# piezo-preamp-tickler_V0-5b.net
KiCad netlist of a schematic drawn in EAGLE
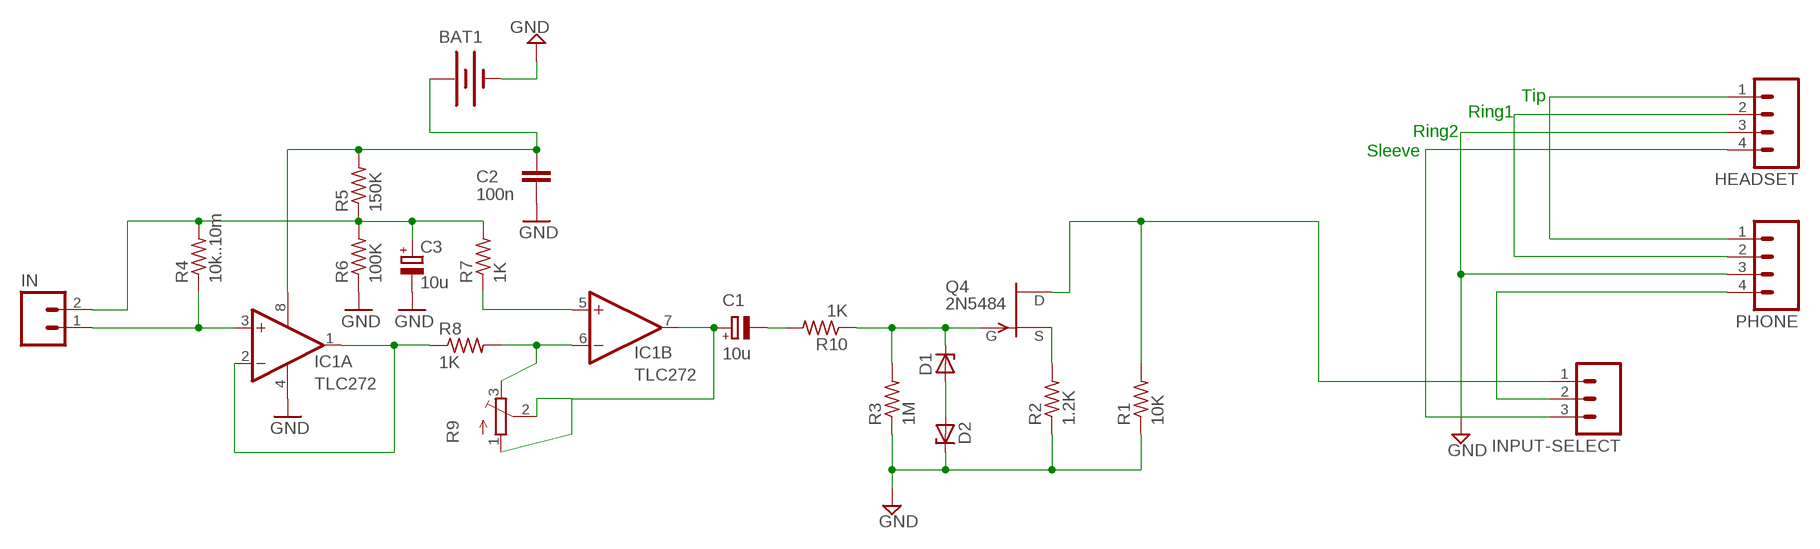
[diagram p0: schematic, sheet 1]

(export (version "E")
  (design (tool "Eeschema 10.0.6"))
  (components
    (comp (ref "BAT1")
      (value "BATTERYA23")
      (footprint "eagle-import:BATTERY-A23")
      (libsource (lib "eagle-import") (part "BATTERYA23"))
    )
    (comp (ref "C1")
      (value "10u")
      (footprint "eagle-import:E2,5-5")
      (libsource (lib "eagle-import") (part "CPOL-EUE2.5-5"))
    )
    (comp (ref "C2")
      (value "100n")
      (footprint "eagle-import:C025-025X050")
      (libsource (lib "eagle-import") (part "C-EU025-025X050"))
    )
    (comp (ref "C3")
      (value "10u")
      (footprint "eagle-import:E2,5-5")
      (libsource (lib "eagle-import") (part "CPOL-EUE2.5-5"))
    )
    (comp (ref "D1")
      (value "1N821")
      (footprint "eagle-import:DO35Z10")
      (libsource (lib "eagle-import") (part "1N821"))
    )
    (comp (ref "D2")
      (value "1N821")
      (footprint "eagle-import:DO35Z10")
      (libsource (lib "eagle-import") (part "1N821"))
    )
    (comp (ref "HEADSET")
      (value "M04LOCK")
      (footprint "eagle-import:1X04_LOCK")
      (libsource (lib "eagle-import") (part "M04LOCK"))
    )
    (comp (ref "IC1")
      (value "TLC272")
      (footprint "eagle-import:DIL08")
      (libsource (lib "eagle-import") (part "TLC272P"))
    )
    (comp (ref "IN")
      (value "M02LOCK")
      (footprint "eagle-import:1X02_LOCK")
      (libsource (lib "eagle-import") (part "M02LOCK"))
    )
    (comp (ref "INPUT-SELECT")
      (value "M03LOCK")
      (footprint "eagle-import:1X03_LOCK")
      (libsource (lib "eagle-import") (part "M03LOCK"))
    )
    (comp (ref "PHONE")
      (value "M04LOCK")
      (footprint "eagle-import:1X04_LOCK")
      (libsource (lib "eagle-import") (part "M04LOCK"))
    )
    (comp (ref "Q4")
      (value "2N5484")
      (footprint "eagle-import:TO92-")
      (libsource (lib "eagle-import") (part "?5482N4"))
    )
    (comp (ref "R1")
      (value "10K")
      (footprint "eagle-import:0204V")
      (libsource (lib "eagle-import") (part "R-US_0204/2V"))
    )
    (comp (ref "R2")
      (value "1.2K")
      (footprint "eagle-import:0204V")
      (libsource (lib "eagle-import") (part "R-US_0204/2V"))
    )
    (comp (ref "R3")
      (value "1M")
      (footprint "eagle-import:0204V")
      (libsource (lib "eagle-import") (part "R-US_0204/2V"))
    )
    (comp (ref "R4")
      (value "10k..10m")
      (footprint "eagle-import:0204V")
      (libsource (lib "eagle-import") (part "R-US_0204/2V"))
    )
    (comp (ref "R5")
      (value "150K")
      (footprint "eagle-import:0204V")
      (libsource (lib "eagle-import") (part "R-US_0204/2V"))
    )
    (comp (ref "R6")
      (value "100K")
      (footprint "eagle-import:0204V")
      (libsource (lib "eagle-import") (part "R-US_0204/2V"))
    )
    (comp (ref "R7")
      (value "1K")
      (footprint "eagle-import:0204V")
      (libsource (lib "eagle-import") (part "R-US_0204/2V"))
    )
    (comp (ref "R8")
      (value "1K")
      (footprint "eagle-import:0204V")
      (libsource (lib "eagle-import") (part "R-US_0204/2V"))
    )
    (comp (ref "R9")
      (value "TRIMPOT3386")
      (footprint "eagle-import:TRIM-3386")
      (libsource (lib "eagle-import") (part "TRIMPOT3386"))
    )
    (comp (ref "R10")
      (value "1K")
      (footprint "eagle-import:0204V")
      (libsource (lib "eagle-import") (part "R-US_0204/2V"))
    )
  )
  (nets
    (net (code "1") (name "GND") (class "Default")
      (node (ref "BAT1") (pin "GND@1") (pinfunction "-_GND@1") (pintype "power_in"))
      (node (ref "C2") (pin "1") (pinfunction "1_1") (pintype "passive"))
      (node (ref "C3") (pin "-") (pinfunction "-_-") (pintype "passive"))
      (node (ref "D2") (pin "C") (pinfunction "C_C") (pintype "passive"))
      (node (ref "HEADSET") (pin "3") (pinfunction "3_3") (pintype "passive"))
      (node (ref "IC1") (pin "4") (pinfunction "V-_4") (pintype "power_in"))
      (node (ref "PHONE") (pin "3") (pinfunction "3_3") (pintype "passive"))
      (node (ref "R1") (pin "1") (pinfunction "1_1") (pintype "passive"))
      (node (ref "R2") (pin "1") (pinfunction "1_1") (pintype "passive"))
      (node (ref "R3") (pin "1") (pinfunction "1_1") (pintype "passive"))
      (node (ref "R6") (pin "1") (pinfunction "1_1") (pintype "passive"))
    )
    (net (code "2") (name "Net-(BAT1-+)") (class "Default")
      (node (ref "BAT1") (pin "PWR@1") (pinfunction "+_PWR@1") (pintype "power_in"))
      (node (ref "C2") (pin "2") (pinfunction "2_2") (pintype "passive"))
      (node (ref "IC1") (pin "8") (pinfunction "V+_8") (pintype "power_in"))
      (node (ref "R5") (pin "2") (pinfunction "2_2") (pintype "passive"))
    )
    (net (code "3") (name "Net-(C1-Pad-)") (class "Default")
      (node (ref "C1") (pin "-") (pinfunction "-_-") (pintype "passive"))
      (node (ref "R10") (pin "2") (pinfunction "2_2") (pintype "passive"))
    )
    (net (code "4") (name "Net-(C3-Pad+)") (class "Default")
      (node (ref "C3") (pin "+") (pinfunction "+_+") (pintype "passive"))
      (node (ref "IN") (pin "2") (pinfunction "2_2") (pintype "passive"))
      (node (ref "R4") (pin "2") (pinfunction "2_2") (pintype "passive"))
      (node (ref "R5") (pin "1") (pinfunction "1_1") (pintype "passive"))
      (node (ref "R6") (pin "2") (pinfunction "2_2") (pintype "passive"))
      (node (ref "R7") (pin "2") (pinfunction "2_2") (pintype "passive"))
    )
    (net (code "5") (name "Net-(D1-PadA)") (class "Default")
      (node (ref "D1") (pin "A") (pinfunction "A_A") (pintype "passive"))
      (node (ref "D2") (pin "A") (pinfunction "A_A") (pintype "passive"))
    )
    (net (code "6") (name "Net-(HEADSET-Pad1)") (class "Default")
      (node (ref "HEADSET") (pin "1") (pinfunction "1_1") (pintype "passive"))
      (node (ref "PHONE") (pin "1") (pinfunction "1_1") (pintype "passive"))
    )
    (net (code "7") (name "Net-(HEADSET-Pad2)") (class "Default")
      (node (ref "HEADSET") (pin "2") (pinfunction "2_2") (pintype "passive"))
      (node (ref "PHONE") (pin "2") (pinfunction "2_2") (pintype "passive"))
    )
    (net (code "8") (name "Net-(HEADSET-Pad4)") (class "Default")
      (node (ref "HEADSET") (pin "4") (pinfunction "4_4") (pintype "passive"))
      (node (ref "INPUT-SELECT") (pin "3") (pinfunction "3_3") (pintype "passive"))
    )
    (net (code "9") (name "Net-(IC1A-+IN)") (class "Default")
      (node (ref "IC1") (pin "3") (pinfunction "+IN_3") (pintype "input"))
      (node (ref "IN") (pin "1") (pinfunction "1_1") (pintype "passive"))
      (node (ref "R4") (pin "1") (pinfunction "1_1") (pintype "passive"))
    )
    (net (code "10") (name "Net-(IC1A--IN)") (class "Default")
      (node (ref "IC1") (pin "1") (pinfunction "OUT_1") (pintype "output"))
      (node (ref "IC1") (pin "2") (pinfunction "-IN_2") (pintype "input"))
      (node (ref "R8") (pin "1") (pinfunction "1_1") (pintype "passive"))
    )
    (net (code "11") (name "Net-(IC1B-+IN)") (class "Default")
      (node (ref "IC1") (pin "5") (pinfunction "+IN_5") (pintype "input"))
      (node (ref "R7") (pin "1") (pinfunction "1_1") (pintype "passive"))
    )
    (net (code "12") (name "Net-(IC1B--IN)") (class "Default")
      (node (ref "IC1") (pin "6") (pinfunction "-IN_6") (pintype "input"))
      (node (ref "R8") (pin "2") (pinfunction "2_2") (pintype "passive"))
      (node (ref "R9") (pin "3") (pinfunction "E_3") (pintype "passive"))
    )
    (net (code "13") (name "Net-(IC1B-OUT)") (class "Default")
      (node (ref "C1") (pin "+") (pinfunction "+_+") (pintype "passive"))
      (node (ref "IC1") (pin "7") (pinfunction "OUT_7") (pintype "output"))
      (node (ref "R9") (pin "1") (pinfunction "A_1") (pintype "passive"))
      (node (ref "R9") (pin "2") (pinfunction "S_2") (pintype "passive"))
    )
    (net (code "14") (name "Net-(INPUT-SELECT-Pad2)") (class "Default")
      (node (ref "INPUT-SELECT") (pin "2") (pinfunction "2_2") (pintype "passive"))
      (node (ref "PHONE") (pin "4") (pinfunction "4_4") (pintype "passive"))
    )
    (net (code "15") (name "Net-(Q4-D)") (class "Default")
      (node (ref "INPUT-SELECT") (pin "1") (pinfunction "1_1") (pintype "passive"))
      (node (ref "Q4") (pin "3") (pinfunction "D_3") (pintype "passive"))
      (node (ref "R1") (pin "2") (pinfunction "2_2") (pintype "passive"))
    )
    (net (code "16") (name "Net-(Q4-G)") (class "Default")
      (node (ref "D1") (pin "C") (pinfunction "C_C") (pintype "passive"))
      (node (ref "Q4") (pin "1") (pinfunction "G_1") (pintype "passive"))
      (node (ref "R10") (pin "1") (pinfunction "1_1") (pintype "passive"))
      (node (ref "R3") (pin "2") (pinfunction "2_2") (pintype "passive"))
    )
    (net (code "17") (name "Net-(Q4-S)") (class "Default")
      (node (ref "Q4") (pin "2") (pinfunction "S_2") (pintype "passive"))
      (node (ref "R2") (pin "2") (pinfunction "2_2") (pintype "passive"))
    )
  )
)
